# power.net
KiCad netlist of a schematic drawn in Altium Designer
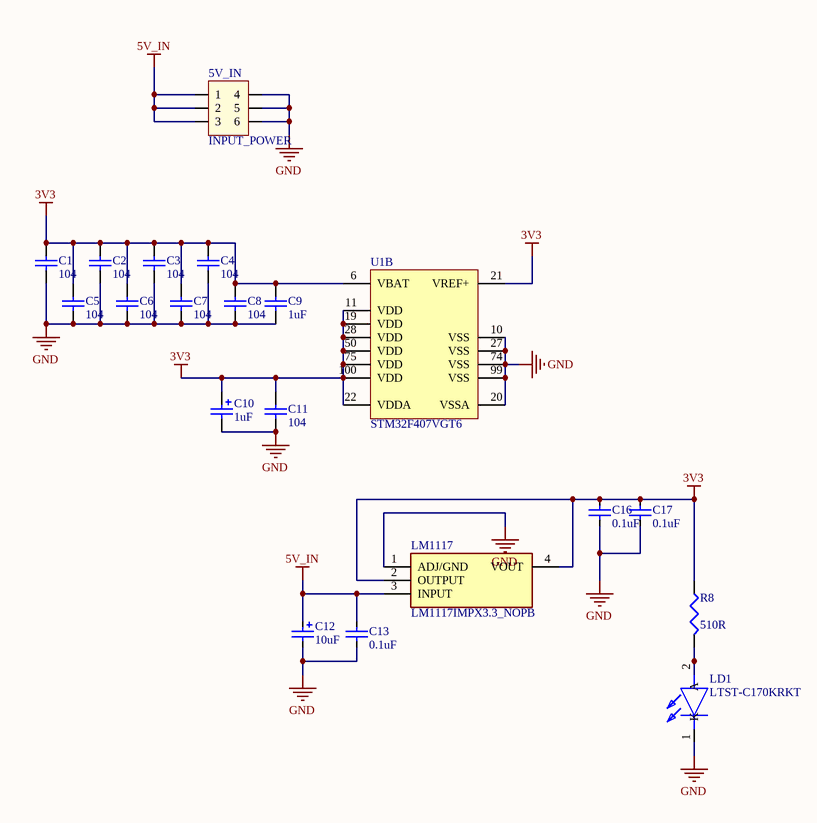
[diagram p0: power.SchDoc]

(export (version "E")
  (design (tool "Eeschema 10.0.6"))
  (components
    (comp (ref "5V_IN")
      (value "INPUT_POWER")
      (footprint "JP3x2")
      (description "Connector 3x2")
      (libsource (lib "syhaunguyen") (part "JP3x2"))
    )
    (comp (ref "C1")
      (value "104")
      (footprint "stm_copter:CAPC2012X98N")
      (description "Capacitor (Semiconductor SIM Model)")
      (fields (field (name "PUBLISHER") "Altium Limited"))
      (libsource (lib "syhaunguyen") (part "Cap Semi"))
    )
    (comp (ref "C2")
      (value "104")
      (footprint "stm_copter:CAPC2012X98N")
      (description "Capacitor (Semiconductor SIM Model)")
      (fields (field (name "PUBLISHER") "Altium Limited"))
      (libsource (lib "syhaunguyen") (part "Cap Semi"))
    )
    (comp (ref "C3")
      (value "104")
      (footprint "stm_copter:CAPC2012X98N")
      (description "Capacitor (Semiconductor SIM Model)")
      (fields (field (name "PUBLISHER") "Altium Limited"))
      (libsource (lib "syhaunguyen") (part "Cap Semi"))
    )
    (comp (ref "C4")
      (value "104")
      (footprint "stm_copter:CAPC2012X98N")
      (description "Capacitor (Semiconductor SIM Model)")
      (fields (field (name "PUBLISHER") "Altium Limited"))
      (libsource (lib "syhaunguyen") (part "Cap Semi"))
    )
    (comp (ref "C5")
      (value "104")
      (footprint "stm_copter:CAPC2012X98N")
      (description "Capacitor (Semiconductor SIM Model)")
      (fields (field (name "PUBLISHER") "Altium Limited"))
      (libsource (lib "syhaunguyen") (part "Cap Semi"))
    )
    (comp (ref "C6")
      (value "104")
      (footprint "stm_copter:CAPC2012X98N")
      (description "Capacitor (Semiconductor SIM Model)")
      (fields (field (name "PUBLISHER") "Altium Limited"))
      (libsource (lib "syhaunguyen") (part "Cap Semi"))
    )
    (comp (ref "C7")
      (value "104")
      (footprint "stm_copter:CAPC2012X98N")
      (description "Capacitor (Semiconductor SIM Model)")
      (fields (field (name "PUBLISHER") "Altium Limited"))
      (libsource (lib "syhaunguyen") (part "Cap Semi"))
    )
    (comp (ref "C8")
      (value "104")
      (footprint "stm_copter:CAPC2012X98N")
      (description "Capacitor (Semiconductor SIM Model)")
      (fields (field (name "PUBLISHER") "Altium Limited"))
      (libsource (lib "syhaunguyen") (part "Cap Semi"))
    )
    (comp (ref "C9")
      (value "1uF")
      (footprint "stm_copter:CAPC1608X90N")
      (description "Capacitor (Semiconductor SIM Model)")
      (fields (field (name "PUBLISHER") "Altium Limited"))
      (libsource (lib "syhaunguyen") (part "Cap Semi"))
    )
    (comp (ref "C10")
      (value "1uF")
      (footprint "stm_copter:CAPPM3216X180N")
      (description "Polarized Capacitor (Axial)")
      (fields (field (name "PUBLISHER") "Altium Limited"))
      (libsource (lib "Miscellaneous Devices") (part "Cap Pol2"))
    )
    (comp (ref "C11")
      (value "104")
      (footprint "stm_copter:CAPC2012X98N")
      (description "Capacitor (Semiconductor SIM Model)")
      (fields (field (name "PUBLISHER") "Altium Limited"))
      (libsource (lib "syhaunguyen") (part "Cap Semi"))
    )
    (comp (ref "C12")
      (value "10uF")
      (footprint "stm_copter:CAPPM3528X210N")
      (description "Tantalum Capacitor")
      (libsource (lib "SCH_Passive") (part "Cap_Tan_1210"))
    )
    (comp (ref "C13")
      (value "0.1uF")
      (footprint "stm_copter:CAPC3216X135N")
      (description "Capacitor")
      (fields (field (name "Comment") "Cap_0603"))
      (libsource (lib "SCH_Passive") (part "Cap_0603"))
    )
    (comp (ref "C16")
      (value "0.1uF")
      (footprint "stm_copter:CAPC3216X135N")
      (description "Capacitor")
      (fields (field (name "Comment") "Cap_0603"))
      (libsource (lib "SCH_Passive") (part "Cap_0603"))
    )
    (comp (ref "C17")
      (value "0.1uF")
      (footprint "stm_copter:CAPC3216X135N")
      (description "Capacitor")
      (fields (field (name "Comment") "Cap_0603"))
      (libsource (lib "SCH_Passive") (part "Cap_0603"))
    )
    (comp (ref "LD1")
      (value "LTST-C170KRKT")
      (footprint "stm_copter:LEDC2012X120N")
      (description "LED")
      (fields
        (field (name "MANUFACTURER_PART_NUMBER") "LTST-C171GKT")
        (field (name "MOUSER PART NUMBER") "859-LTST-C171GKT")
      )
      (libsource (lib "DRV8323_Lib") (part "LTST-C171GKT"))
    )
    (comp (ref "LM1117")
      (value "LM1117IMPX3.3_NOPB")
      (footprint "SamacSys:SOT230P700X180-4N")
      (description "Integrated Circuit")
      (fields (field (name "MANUFACTURER_PART_NUMBER") "LM1117IMPX3.3/NOPB"))
      (libsource (lib "*") (part "LM1117IMPX3.3_NOPB"))
    )
    (comp (ref "R8")
      (value "510R")
      (footprint "stm_copter:RESC1608X55N")
      (description "Resistor")
      (fields (field (name "PUBLISHER") "Altium Limited"))
      (libsource (lib "Miscellaneous Devices") (part "Res3"))
    )
    (comp (ref "U1")
      (value "STM32F407VGT6")
      (footprint "STM-LQFP100_N")
      (fields (field (name "MANUFACTURER") "STMicroelectronics"))
      (libsource (lib "STMicroelectronics STM32 F4") (part "STM32F407VGT6"))
    )
  )
  (nets
    (net (code "1") (name "3V3") (class "Default")
      (node (ref "C1") (pin "1") (pinfunction "1_1") (pintype "passive"))
      (node (ref "C10") (pin "1") (pinfunction "1_1") (pintype "passive"))
      (node (ref "C11") (pin "1") (pinfunction "1_1") (pintype "passive"))
      (node (ref "C16") (pin "2") (pinfunction "2_2") (pintype "passive"))
      (node (ref "C17") (pin "2") (pinfunction "2_2") (pintype "passive"))
      (node (ref "C2") (pin "1") (pinfunction "1_1") (pintype "passive"))
      (node (ref "C3") (pin "1") (pinfunction "1_1") (pintype "passive"))
      (node (ref "C4") (pin "1") (pinfunction "1_1") (pintype "passive"))
      (node (ref "C5") (pin "1") (pinfunction "1_1") (pintype "passive"))
      (node (ref "C6") (pin "1") (pinfunction "1_1") (pintype "passive"))
      (node (ref "C7") (pin "1") (pinfunction "1_1") (pintype "passive"))
      (node (ref "C8") (pin "1") (pinfunction "1_1") (pintype "passive"))
      (node (ref "C9") (pin "2") (pinfunction "2_2") (pintype "passive"))
      (node (ref "LM1117") (pin "2") (pinfunction "OUTPUT_2") (pintype "passive"))
      (node (ref "LM1117") (pin "4") (pinfunction "VOUT_4") (pintype "passive"))
      (node (ref "R8") (pin "1") (pinfunction "1_1") (pintype "passive"))
      (node (ref "U1") (pin "100") (pinfunction "VDD_100") (pintype "power_in"))
      (node (ref "U1") (pin "11") (pinfunction "VDD_11") (pintype "power_in"))
      (node (ref "U1") (pin "19") (pinfunction "VDD_19") (pintype "power_in"))
      (node (ref "U1") (pin "21") (pinfunction "VREF+_21") (pintype "power_in"))
      (node (ref "U1") (pin "22") (pinfunction "VDDA_22") (pintype "power_in"))
      (node (ref "U1") (pin "28") (pinfunction "VDD_28") (pintype "power_in"))
      (node (ref "U1") (pin "50") (pinfunction "VDD_50") (pintype "power_in"))
      (node (ref "U1") (pin "6") (pinfunction "VBAT_6") (pintype "power_in"))
      (node (ref "U1") (pin "75") (pinfunction "VDD_75") (pintype "power_in"))
    )
    (net (code "2") (name "5V_IN") (class "Default")
      (node (ref "5V_IN") (pin "1") (pinfunction "1_1") (pintype "passive"))
      (node (ref "5V_IN") (pin "2") (pinfunction "2_2") (pintype "passive"))
      (node (ref "5V_IN") (pin "3") (pinfunction "3_3") (pintype "passive"))
      (node (ref "C12") (pin "1") (pinfunction "1_1") (pintype "passive"))
      (node (ref "C13") (pin "2") (pinfunction "2_2") (pintype "passive"))
      (node (ref "LM1117") (pin "3") (pinfunction "INPUT_3") (pintype "passive"))
    )
    (net (code "3") (name "GND") (class "Default")
      (node (ref "5V_IN") (pin "4") (pinfunction "4_4") (pintype "passive"))
      (node (ref "5V_IN") (pin "5") (pinfunction "5_5") (pintype "passive"))
      (node (ref "5V_IN") (pin "6") (pinfunction "6_6") (pintype "passive"))
      (node (ref "C1") (pin "2") (pinfunction "2_2") (pintype "passive"))
      (node (ref "C10") (pin "2") (pinfunction "2_2") (pintype "passive"))
      (node (ref "C11") (pin "2") (pinfunction "2_2") (pintype "passive"))
      (node (ref "C12") (pin "2") (pinfunction "2_2") (pintype "passive"))
      (node (ref "C13") (pin "1") (pinfunction "1_1") (pintype "passive"))
      (node (ref "C16") (pin "1") (pinfunction "1_1") (pintype "passive"))
      (node (ref "C17") (pin "1") (pinfunction "1_1") (pintype "passive"))
      (node (ref "C2") (pin "2") (pinfunction "2_2") (pintype "passive"))
      (node (ref "C3") (pin "2") (pinfunction "2_2") (pintype "passive"))
      (node (ref "C4") (pin "2") (pinfunction "2_2") (pintype "passive"))
      (node (ref "C5") (pin "2") (pinfunction "2_2") (pintype "passive"))
      (node (ref "C6") (pin "2") (pinfunction "2_2") (pintype "passive"))
      (node (ref "C7") (pin "2") (pinfunction "2_2") (pintype "passive"))
      (node (ref "C8") (pin "2") (pinfunction "2_2") (pintype "passive"))
      (node (ref "C9") (pin "1") (pinfunction "1_1") (pintype "passive"))
      (node (ref "LD1") (pin "1") (pinfunction "K_1") (pintype "passive"))
      (node (ref "LM1117") (pin "1") (pinfunction "ADJ/GND_1") (pintype "passive"))
      (node (ref "U1") (pin "10") (pinfunction "VSS_10") (pintype "power_in"))
      (node (ref "U1") (pin "20") (pinfunction "VSSA_20") (pintype "power_in"))
      (node (ref "U1") (pin "27") (pinfunction "VSS_27") (pintype "power_in"))
      (node (ref "U1") (pin "74") (pinfunction "VSS_74") (pintype "power_in"))
      (node (ref "U1") (pin "99") (pinfunction "VSS_99") (pintype "power_in"))
    )
    (net (code "4") (name "Net-(LD1-A)") (class "Default")
      (node (ref "LD1") (pin "2") (pinfunction "A_2") (pintype "passive"))
      (node (ref "R8") (pin "2") (pinfunction "2_2") (pintype "passive"))
    )
  )
)
